# Penguin_Base.net
KiCad netlist of a schematic drawn in Altium Designer
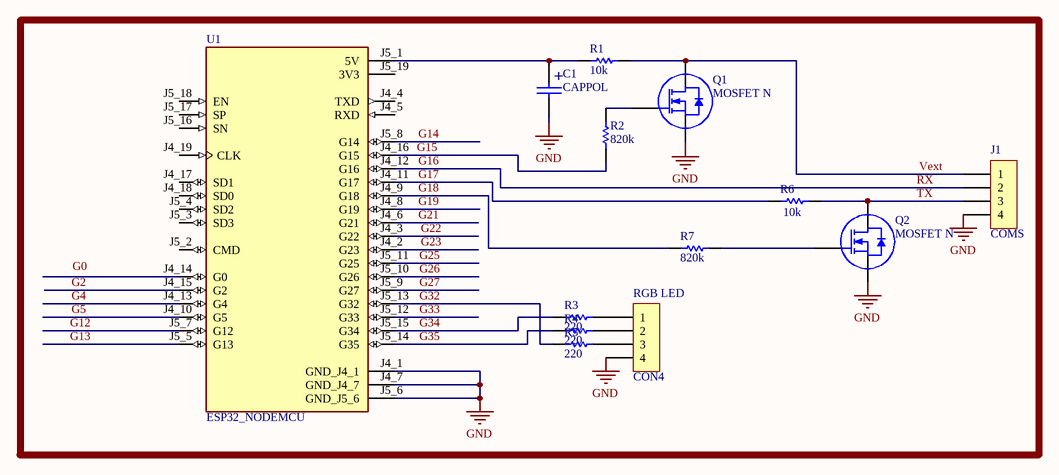
[diagram p0: Penguin_Base.SchDoc]

(export (version "E")
  (design (tool "Eeschema 10.0.6"))
  (components
    (comp (ref "C1") (value "CAPPOL") (footprint "CAP100RP") (libsource (lib "LIBEBAL") (part "CAPPOL")))
    (comp (ref "J1") (value "COMS") (footprint "SIP4") (libsource (lib "LIBEBAL") (part "CON4")))
    (comp (ref "Q1") (value "MOSFET N") (footprint "JUMPER3") (libsource (lib "LIBEBAL") (part "MOSFET N")))
    (comp (ref "Q2") (value "MOSFET N") (footprint "JUMPER3") (libsource (lib "LIBEBAL") (part "MOSFET N")))
    (comp (ref "R1") (value "10k") (footprint "RES400") (libsource (lib "LIBEBAL") (part "RES")))
    (comp (ref "R2") (value "820k") (footprint "RES400") (libsource (lib "LIBEBAL") (part "RES")))
    (comp (ref "R3") (value "220") (footprint "RES400") (libsource (lib "LIBEBAL") (part "RES")))
    (comp (ref "R4") (value "220") (footprint "RES400") (libsource (lib "LIBEBAL") (part "RES")))
    (comp (ref "R5") (value "220") (footprint "RES400") (libsource (lib "LIBEBAL") (part "RES")))
    (comp (ref "R6") (value "10k") (footprint "RES400") (libsource (lib "LIBEBAL") (part "RES")))
    (comp (ref "R7") (value "820k") (footprint "RES400") (libsource (lib "LIBEBAL") (part "RES")))
    (comp (ref "RGB LED") (value "CON4") (footprint "SIP4") (libsource (lib "LIBEBAL") (part "CON4")))
    (comp (ref "U1")
      (value "ESP32_NODEMCU")
      (footprint "MODULE_ESP32_NODEMCU")
      (fields (field (name "MP") "ESP32 NodeMCU") (field (name "MF") "Espressif Systems"))
      (libsource (lib "ESP32_NODEMCU") (part "ESP32_NODEMCU"))
    )
  )
  (nets
    (net (code "2") (name "/G2") (class "Default")
      (node (ref "U1") (pin "J4_15") (pinfunction "G2_J4_15") (pintype "bidirectional"))
    )
    (net (code "3") (name "/G4") (class "Default")
      (node (ref "U1") (pin "J4_13") (pinfunction "G4_J4_13") (pintype "bidirectional"))
    )
    (net (code "4") (name "/G5") (class "Default")
      (node (ref "U1") (pin "J4_10") (pinfunction "G5_J4_10") (pintype "bidirectional"))
    )
    (net (code "5") (name "/G12") (class "Default")
      (node (ref "U1") (pin "J5_7") (pinfunction "G12_J5_7") (pintype "bidirectional"))
    )
    (net (code "6") (name "/G13") (class "Default")
      (node (ref "U1") (pin "J5_5") (pinfunction "G13_J5_5") (pintype "bidirectional"))
    )
    (net (code "7") (name "/G14") (class "Default")
      (node (ref "U1") (pin "J5_8") (pinfunction "G14_J5_8") (pintype "bidirectional"))
    )
    (net (code "8") (name "/G15") (class "Default")
      (node (ref "R2") (pin "1") (pinfunction "1_1") (pintype "passive"))
      (node (ref "U1") (pin "J4_16") (pinfunction "G15_J4_16") (pintype "bidirectional"))
    )
    (net (code "9") (name "/G16") (class "Default")
      (node (ref "J1") (pin "2") (pinfunction "2_2") (pintype "passive"))
      (node (ref "U1") (pin "J4_12") (pinfunction "G16_J4_12") (pintype "bidirectional"))
    )
    (net (code "10") (name "/G17") (class "Default")
      (node (ref "R6") (pin "1") (pinfunction "1_1") (pintype "passive"))
      (node (ref "U1") (pin "J4_11") (pinfunction "G17_J4_11") (pintype "bidirectional"))
    )
    (net (code "11") (name "/G18") (class "Default")
      (node (ref "R7") (pin "1") (pinfunction "1_1") (pintype "passive"))
      (node (ref "U1") (pin "J4_9") (pinfunction "G18_J4_9") (pintype "bidirectional"))
    )
    (net (code "12") (name "/G19") (class "Default")
      (node (ref "U1") (pin "J4_8") (pinfunction "G19_J4_8") (pintype "bidirectional"))
    )
    (net (code "13") (name "/G21") (class "Default")
      (node (ref "U1") (pin "J4_6") (pinfunction "G21_J4_6") (pintype "bidirectional"))
    )
    (net (code "14") (name "/G22") (class "Default")
      (node (ref "U1") (pin "J4_3") (pinfunction "G22_J4_3") (pintype "bidirectional"))
    )
    (net (code "15") (name "/G23") (class "Default")
      (node (ref "U1") (pin "J4_2") (pinfunction "G23_J4_2") (pintype "bidirectional"))
    )
    (net (code "16") (name "/G25") (class "Default")
      (node (ref "U1") (pin "J5_11") (pinfunction "G25_J5_11") (pintype "bidirectional"))
    )
    (net (code "17") (name "/G26") (class "Default")
      (node (ref "U1") (pin "J5_10") (pinfunction "G26_J5_10") (pintype "bidirectional"))
    )
    (net (code "18") (name "/G27") (class "Default")
      (node (ref "U1") (pin "J5_9") (pinfunction "G27_J5_9") (pintype "bidirectional"))
    )
    (net (code "19") (name "/G32") (class "Default")
      (node (ref "R5") (pin "1") (pinfunction "1_1") (pintype "passive"))
      (node (ref "U1") (pin "J5_13") (pinfunction "G32_J5_13") (pintype "bidirectional"))
    )
    (net (code "20") (name "/G33") (class "Default")
      (node (ref "U1") (pin "J5_12") (pinfunction "G33_J5_12") (pintype "bidirectional"))
    )
    (net (code "21") (name "/G34") (class "Default")
      (node (ref "R3") (pin "1") (pinfunction "1_1") (pintype "passive"))
      (node (ref "U1") (pin "J5_15") (pinfunction "G34_J5_15") (pintype "bidirectional"))
    )
    (net (code "22") (name "/G35") (class "Default")
      (node (ref "R4") (pin "1") (pinfunction "1_1") (pintype "passive"))
      (node (ref "U1") (pin "J5_14") (pinfunction "G35_J5_14") (pintype "bidirectional"))
    )
    (net (code "23") (name "/TX") (class "Default")
      (node (ref "J1") (pin "3") (pinfunction "3_3") (pintype "passive"))
      (node (ref "Q2") (pin "2") (pinfunction "D_2") (pintype "passive"))
      (node (ref "R6") (pin "2") (pinfunction "2_2") (pintype "passive"))
    )
    (net (code "24") (name "/Vext") (class "Default")
      (node (ref "J1") (pin "1") (pinfunction "1_1") (pintype "passive"))
      (node (ref "Q1") (pin "2") (pinfunction "D_2") (pintype "passive"))
      (node (ref "R1") (pin "2") (pinfunction "2_2") (pintype "passive"))
    )
    (net (code "25") (name "GND") (class "Default")
      (node (ref "C1") (pin "2") (pinfunction "2_2") (pintype "passive"))
      (node (ref "J1") (pin "4") (pinfunction "4_4") (pintype "passive"))
      (node (ref "Q1") (pin "3") (pinfunction "S_3") (pintype "passive"))
      (node (ref "Q2") (pin "3") (pinfunction "S_3") (pintype "passive"))
      (node (ref "RGB LED") (pin "4") (pinfunction "4_4") (pintype "passive"))
      (node (ref "U1") (pin "J4_1") (pinfunction "GND_J4_1_J4_1") (pintype "power_in"))
      (node (ref "U1") (pin "J4_7") (pinfunction "GND_J4_7_J4_7") (pintype "power_in"))
      (node (ref "U1") (pin "J5_6") (pinfunction "GND_J5_6_J5_6") (pintype "power_in"))
    )
    (net (code "26") (name "Net-(Q1-G)") (class "Default")
      (node (ref "Q1") (pin "1") (pinfunction "G_1") (pintype "passive"))
      (node (ref "R2") (pin "2") (pinfunction "2_2") (pintype "passive"))
    )
    (net (code "27") (name "Net-(Q2-G)") (class "Default")
      (node (ref "Q2") (pin "1") (pinfunction "G_1") (pintype "passive"))
      (node (ref "R7") (pin "2") (pinfunction "2_2") (pintype "passive"))
    )
    (net (code "28") (name "Net-(R3-Pad2)") (class "Default")
      (node (ref "R3") (pin "2") (pinfunction "2_2") (pintype "passive"))
      (node (ref "RGB LED") (pin "1") (pinfunction "1_1") (pintype "passive"))
    )
    (net (code "29") (name "Net-(R4-Pad2)") (class "Default")
      (node (ref "R4") (pin "2") (pinfunction "2_2") (pintype "passive"))
      (node (ref "RGB LED") (pin "2") (pinfunction "2_2") (pintype "passive"))
    )
    (net (code "30") (name "Net-(R5-Pad2)") (class "Default")
      (node (ref "R5") (pin "2") (pinfunction "2_2") (pintype "passive"))
      (node (ref "RGB LED") (pin "3") (pinfunction "3_3") (pintype "passive"))
    )
    (net (code "31") (name "Net-(U1-5V)") (class "Default")
      (node (ref "C1") (pin "1") (pinfunction "1_1") (pintype "passive"))
      (node (ref "R1") (pin "1") (pinfunction "1_1") (pintype "passive"))
      (node (ref "U1") (pin "J5_1") (pinfunction "5V_J5_1") (pintype "power_in"))
    )
    (net (code "32") (name "unconnected-(U1-3V3-PadJ5_19)") (class "Default")
      (node (ref "U1") (pin "J5_19") (pinfunction "3V3_J5_19") (pintype "power_in"))
    )
    (net (code "33") (name "unconnected-(U1-CLK-PadJ4_19)") (class "Default")
      (node (ref "U1") (pin "J4_19") (pinfunction "CLK_J4_19") (pintype "input"))
    )
    (net (code "34") (name "unconnected-(U1-CMD-PadJ5_2)") (class "Default")
      (node (ref "U1") (pin "J5_2") (pinfunction "CMD_J5_2") (pintype "bidirectional"))
    )
    (net (code "35") (name "unconnected-(U1-EN-PadJ5_18)") (class "Default")
      (node (ref "U1") (pin "J5_18") (pinfunction "EN_J5_18") (pintype "input"))
    )
    (net (code "36") (name "unconnected-(U1-G0-PadJ4_14)") (class "Default")
      (node (ref "U1") (pin "J4_14") (pinfunction "G0_J4_14") (pintype "bidirectional"))
    )
    (net (code "37") (name "unconnected-(U1-RXD-PadJ4_5)") (class "Default")
      (node (ref "U1") (pin "J4_5") (pinfunction "RXD_J4_5") (pintype "input"))
    )
    (net (code "38") (name "unconnected-(U1-SD0-PadJ4_18)") (class "Default")
      (node (ref "U1") (pin "J4_18") (pinfunction "SD0_J4_18") (pintype "bidirectional"))
    )
    (net (code "39") (name "unconnected-(U1-SD1-PadJ4_17)") (class "Default")
      (node (ref "U1") (pin "J4_17") (pinfunction "SD1_J4_17") (pintype "bidirectional"))
    )
    (net (code "40") (name "unconnected-(U1-SD2-PadJ5_4)") (class "Default")
      (node (ref "U1") (pin "J5_4") (pinfunction "SD2_J5_4") (pintype "bidirectional"))
    )
    (net (code "41") (name "unconnected-(U1-SD3-PadJ5_3)") (class "Default")
      (node (ref "U1") (pin "J5_3") (pinfunction "SD3_J5_3") (pintype "bidirectional"))
    )
    (net (code "42") (name "unconnected-(U1-SN-PadJ5_16)") (class "Default")
      (node (ref "U1") (pin "J5_16") (pinfunction "SN_J5_16") (pintype "input"))
    )
    (net (code "43") (name "unconnected-(U1-SP-PadJ5_17)") (class "Default")
      (node (ref "U1") (pin "J5_17") (pinfunction "SP_J5_17") (pintype "input"))
    )
    (net (code "44") (name "unconnected-(U1-TXD-PadJ4_4)") (class "Default")
      (node (ref "U1") (pin "J4_4") (pinfunction "TXD_J4_4") (pintype "output"))
    )
  )
)
